# board.net
KiCad netlist of a schematic drawn in EAGLE
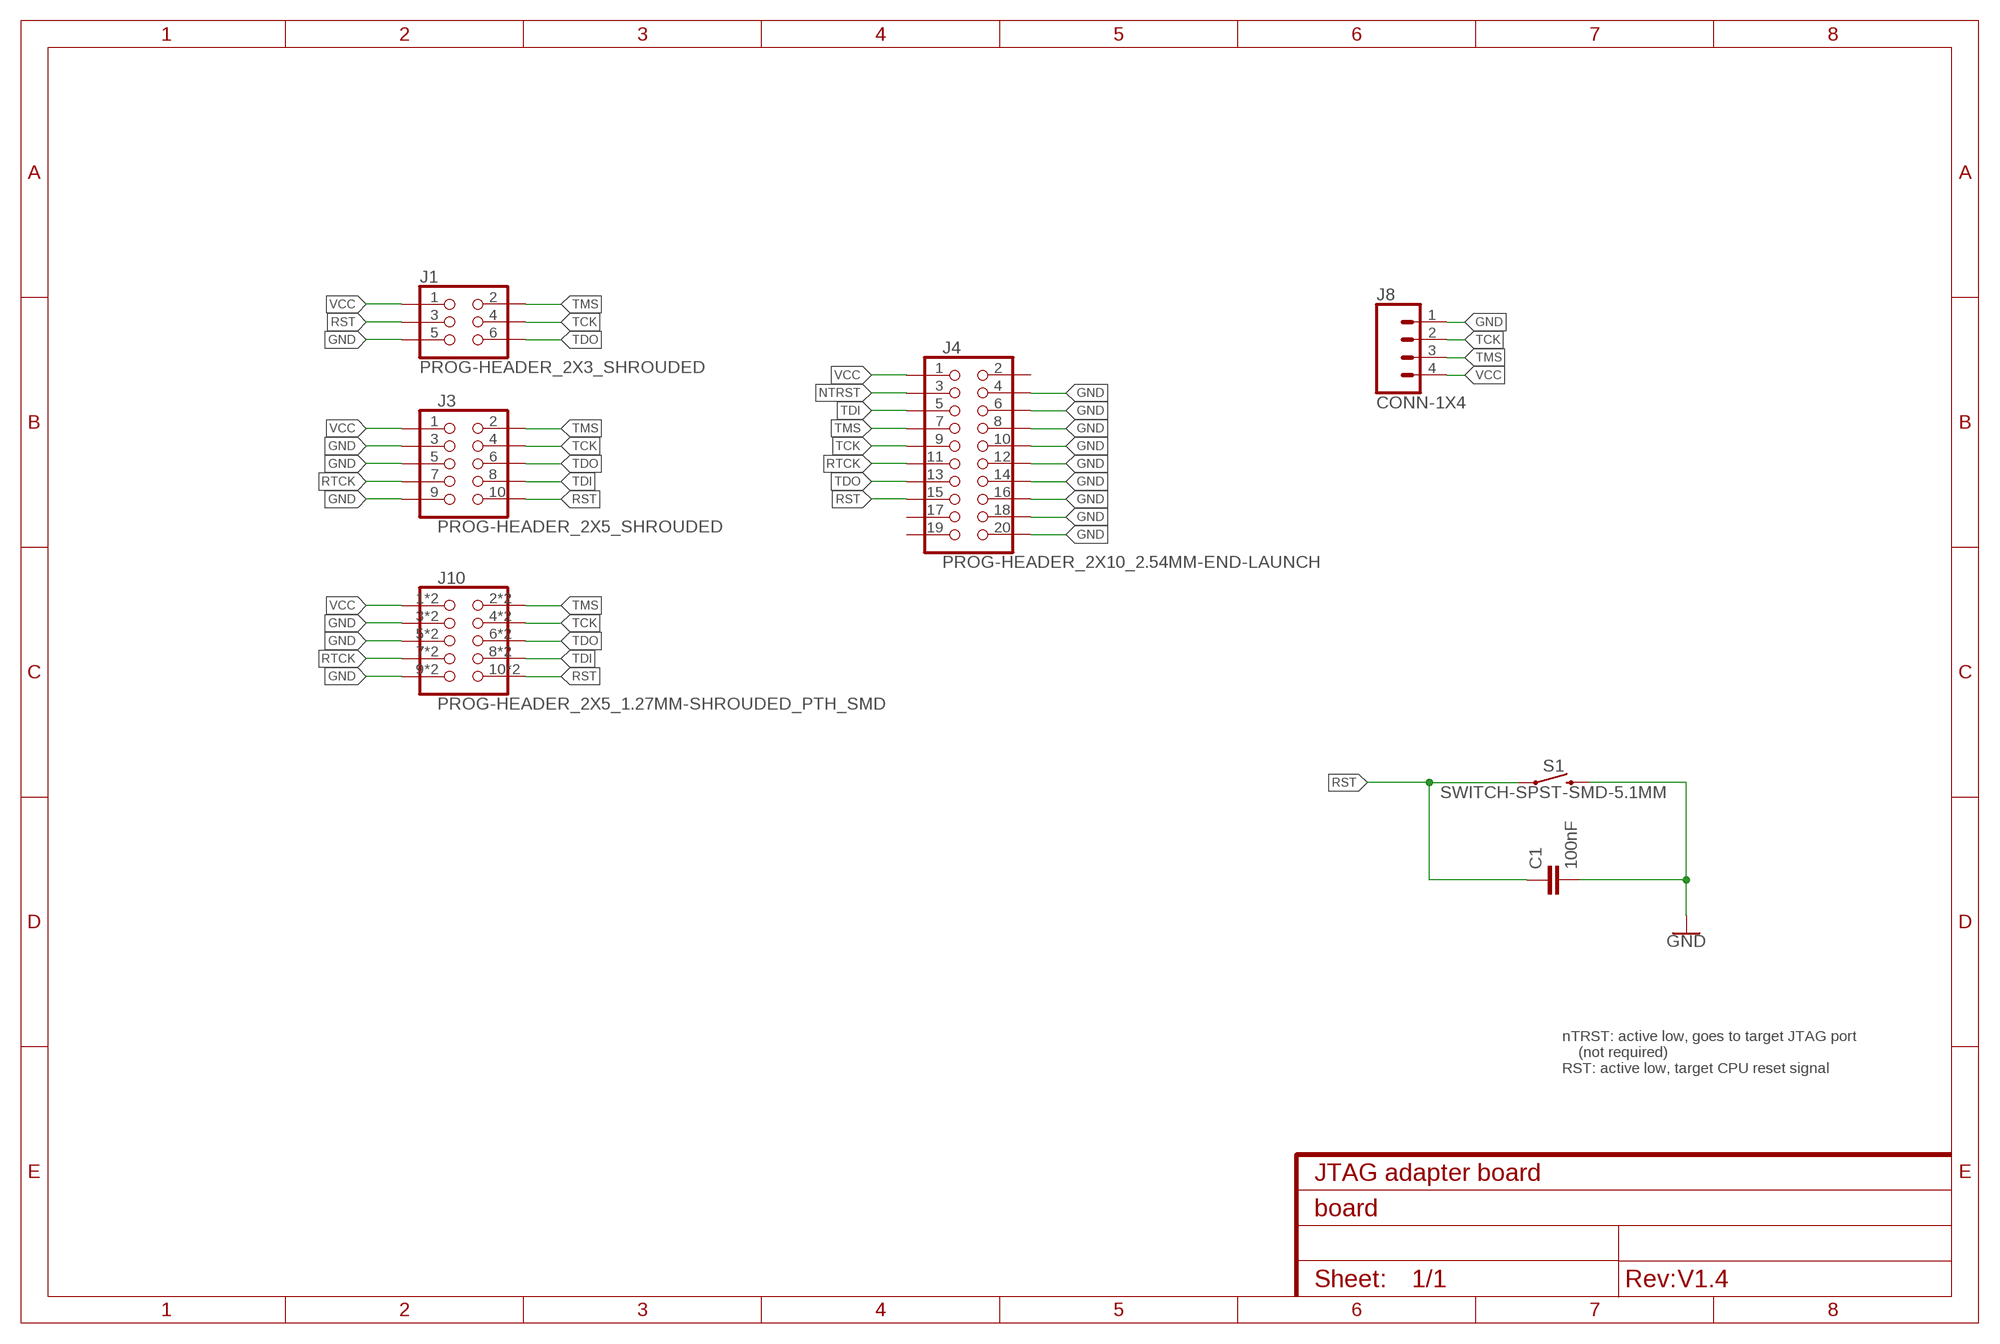
[diagram p0: schematic, sheet 1]

(export (version "E")
  (design (tool "Eeschema 10.0.6"))
  (components
    (comp (ref "C1")
      (value "100nF")
      (footprint "eagle-import:C0603")
      (libsource (lib "eagle-import") (part "C-NON-POLC0603"))
    )
    (comp (ref "J1")
      (value "PROG-HEADER_2X3_SHROUDED")
      (footprint "eagle-import:2X3-2.54MM-SHROUDED")
      (libsource (lib "eagle-import") (part "PROG-HEADER_2X3_SHROUDED"))
    )
    (comp (ref "J3")
      (value "PROG-HEADER_2X5_SHROUDED")
      (footprint "eagle-import:2X5-2.54MM-SHROUDED")
      (libsource (lib "eagle-import") (part "PROG-HEADER_2X5_SHROUDED"))
    )
    (comp (ref "J4")
      (value "PROG-HEADER_2X10_2.54MM-END-LAUNCH")
      (footprint "eagle-import:2X10-2.54MM-END-LAUNCH")
      (libsource (lib "eagle-import") (part "PROG-HEADER_2X10_2.54MM-END-LAUNCH"))
    )
    (comp (ref "J8")
      (value "CONN-1X4")
      (footprint "eagle-import:XH-4P-2.54MM")
      (libsource (lib "eagle-import") (part "CONN-1X4"))
    )
    (comp (ref "J10")
      (value "PROG-HEADER_2X5_1.27MM-SHROUDED_PTH_SMD")
      (footprint "eagle-import:2X5-1.27MM-SHROUDED_PTH+SMD")
      (libsource (lib "eagle-import") (part "PROG-HEADER_2X5_1.27MM-SHROUDED_PTH_SMD"))
    )
    (comp (ref "S1")
      (value "SWITCH-SPST-SMD-5.1MM")
      (footprint "eagle-import:TACTILE_SWITCH_SMD_5.1MM")
      (libsource (lib "eagle-import") (part "SWITCH-SPST-SMD-5.1MM"))
    )
  )
  (nets
    (net (code "1") (name "/2") (class "Default")
      (node (ref "J4") (pin "2") (pinfunction "2_2") (pintype "power_in"))
    )
    (net (code "2") (name "GND") (class "Default")
      (node (ref "C1") (pin "2") (pinfunction "2_2") (pintype "passive"))
      (node (ref "J1") (pin "5") (pinfunction "5_5") (pintype "passive"))
      (node (ref "J10") (pin "13") (pinfunction "3_13") (pintype "passive"))
      (node (ref "J10") (pin "15") (pinfunction "5_15") (pintype "passive"))
      (node (ref "J10") (pin "19") (pinfunction "9_19") (pintype "passive"))
      (node (ref "J10") (pin "3") (pinfunction "3_3") (pintype "passive"))
      (node (ref "J10") (pin "5") (pinfunction "5_5") (pintype "passive"))
      (node (ref "J10") (pin "9") (pinfunction "9_9") (pintype "passive"))
      (node (ref "J3") (pin "3") (pinfunction "3_3") (pintype "passive"))
      (node (ref "J3") (pin "5") (pinfunction "5_5") (pintype "passive"))
      (node (ref "J3") (pin "9") (pinfunction "9_9") (pintype "passive"))
      (node (ref "J4") (pin "10") (pinfunction "10_10") (pintype "power_in"))
      (node (ref "J4") (pin "12") (pinfunction "12_12") (pintype "power_in"))
      (node (ref "J4") (pin "14") (pinfunction "14_14") (pintype "power_in"))
      (node (ref "J4") (pin "16") (pinfunction "16_16") (pintype "power_in"))
      (node (ref "J4") (pin "18") (pinfunction "18_18") (pintype "power_in"))
      (node (ref "J4") (pin "20") (pinfunction "20_20") (pintype "power_in"))
      (node (ref "J4") (pin "4") (pinfunction "4_4") (pintype "power_in"))
      (node (ref "J4") (pin "6") (pinfunction "6_6") (pintype "power_in"))
      (node (ref "J4") (pin "8") (pinfunction "8_8") (pintype "power_in"))
      (node (ref "J8") (pin "1") (pinfunction "1_1") (pintype "passive"))
      (node (ref "S1") (pin "3") (pinfunction "2_3") (pintype "passive"))
    )
    (net (code "3") (name "NTRST") (class "Default")
      (node (ref "J4") (pin "3") (pinfunction "3_3") (pintype "passive"))
    )
    (net (code "4") (name "RST") (class "Default")
      (node (ref "C1") (pin "1") (pinfunction "1_1") (pintype "passive"))
      (node (ref "J1") (pin "3") (pinfunction "3_3") (pintype "passive"))
      (node (ref "J10") (pin "10") (pinfunction "10_10") (pintype "power_in"))
      (node (ref "J10") (pin "20") (pinfunction "10_20") (pintype "power_in"))
      (node (ref "J3") (pin "10") (pinfunction "10_10") (pintype "power_in"))
      (node (ref "J4") (pin "15") (pinfunction "15_15") (pintype "passive"))
      (node (ref "S1") (pin "1") (pinfunction "1_1") (pintype "passive"))
    )
    (net (code "5") (name "RTCK") (class "Default")
      (node (ref "J10") (pin "17") (pinfunction "7_17") (pintype "passive"))
      (node (ref "J10") (pin "7") (pinfunction "7_7") (pintype "passive"))
      (node (ref "J3") (pin "7") (pinfunction "7_7") (pintype "passive"))
      (node (ref "J4") (pin "11") (pinfunction "11_11") (pintype "passive"))
    )
    (net (code "6") (name "TCK") (class "Default")
      (node (ref "J1") (pin "4") (pinfunction "4_4") (pintype "passive"))
      (node (ref "J10") (pin "14") (pinfunction "4_14") (pintype "power_in"))
      (node (ref "J10") (pin "4") (pinfunction "4_4") (pintype "power_in"))
      (node (ref "J3") (pin "4") (pinfunction "4_4") (pintype "power_in"))
      (node (ref "J4") (pin "9") (pinfunction "9_9") (pintype "passive"))
      (node (ref "J8") (pin "2") (pinfunction "2_2") (pintype "passive"))
    )
    (net (code "7") (name "TDI") (class "Default")
      (node (ref "J10") (pin "18") (pinfunction "8_18") (pintype "power_in"))
      (node (ref "J10") (pin "8") (pinfunction "8_8") (pintype "power_in"))
      (node (ref "J3") (pin "8") (pinfunction "8_8") (pintype "power_in"))
      (node (ref "J4") (pin "5") (pinfunction "5_5") (pintype "passive"))
    )
    (net (code "8") (name "TDO") (class "Default")
      (node (ref "J1") (pin "6") (pinfunction "6_6") (pintype "passive"))
      (node (ref "J10") (pin "16") (pinfunction "6_16") (pintype "power_in"))
      (node (ref "J10") (pin "6") (pinfunction "6_6") (pintype "power_in"))
      (node (ref "J3") (pin "6") (pinfunction "6_6") (pintype "power_in"))
      (node (ref "J4") (pin "13") (pinfunction "13_13") (pintype "passive"))
    )
    (net (code "9") (name "TMS") (class "Default")
      (node (ref "J1") (pin "2") (pinfunction "2_2") (pintype "passive"))
      (node (ref "J10") (pin "12") (pinfunction "2_12") (pintype "power_in"))
      (node (ref "J10") (pin "2") (pinfunction "2_2") (pintype "power_in"))
      (node (ref "J3") (pin "2") (pinfunction "2_2") (pintype "power_in"))
      (node (ref "J4") (pin "7") (pinfunction "7_7") (pintype "passive"))
      (node (ref "J8") (pin "3") (pinfunction "3_3") (pintype "passive"))
    )
    (net (code "10") (name "VCC") (class "Default")
      (node (ref "J1") (pin "1") (pinfunction "1_1") (pintype "passive"))
      (node (ref "J10") (pin "1") (pinfunction "1_1") (pintype "passive"))
      (node (ref "J10") (pin "11") (pinfunction "1_11") (pintype "passive"))
      (node (ref "J3") (pin "1") (pinfunction "1_1") (pintype "passive"))
      (node (ref "J4") (pin "1") (pinfunction "1_1") (pintype "passive"))
      (node (ref "J8") (pin "4") (pinfunction "4_4") (pintype "passive"))
    )
    (net (code "11") (name "unconnected-(J4-Pad17)") (class "Default")
      (node (ref "J4") (pin "17") (pinfunction "17_17") (pintype "passive"))
    )
    (net (code "12") (name "unconnected-(J4-Pad19)") (class "Default")
      (node (ref "J4") (pin "19") (pinfunction "19_19") (pintype "passive"))
    )
  )
)
